# SCH_Pathfinder-V1_2025-12-04.net
KiCad netlist of a schematic drawn in EasyEDA
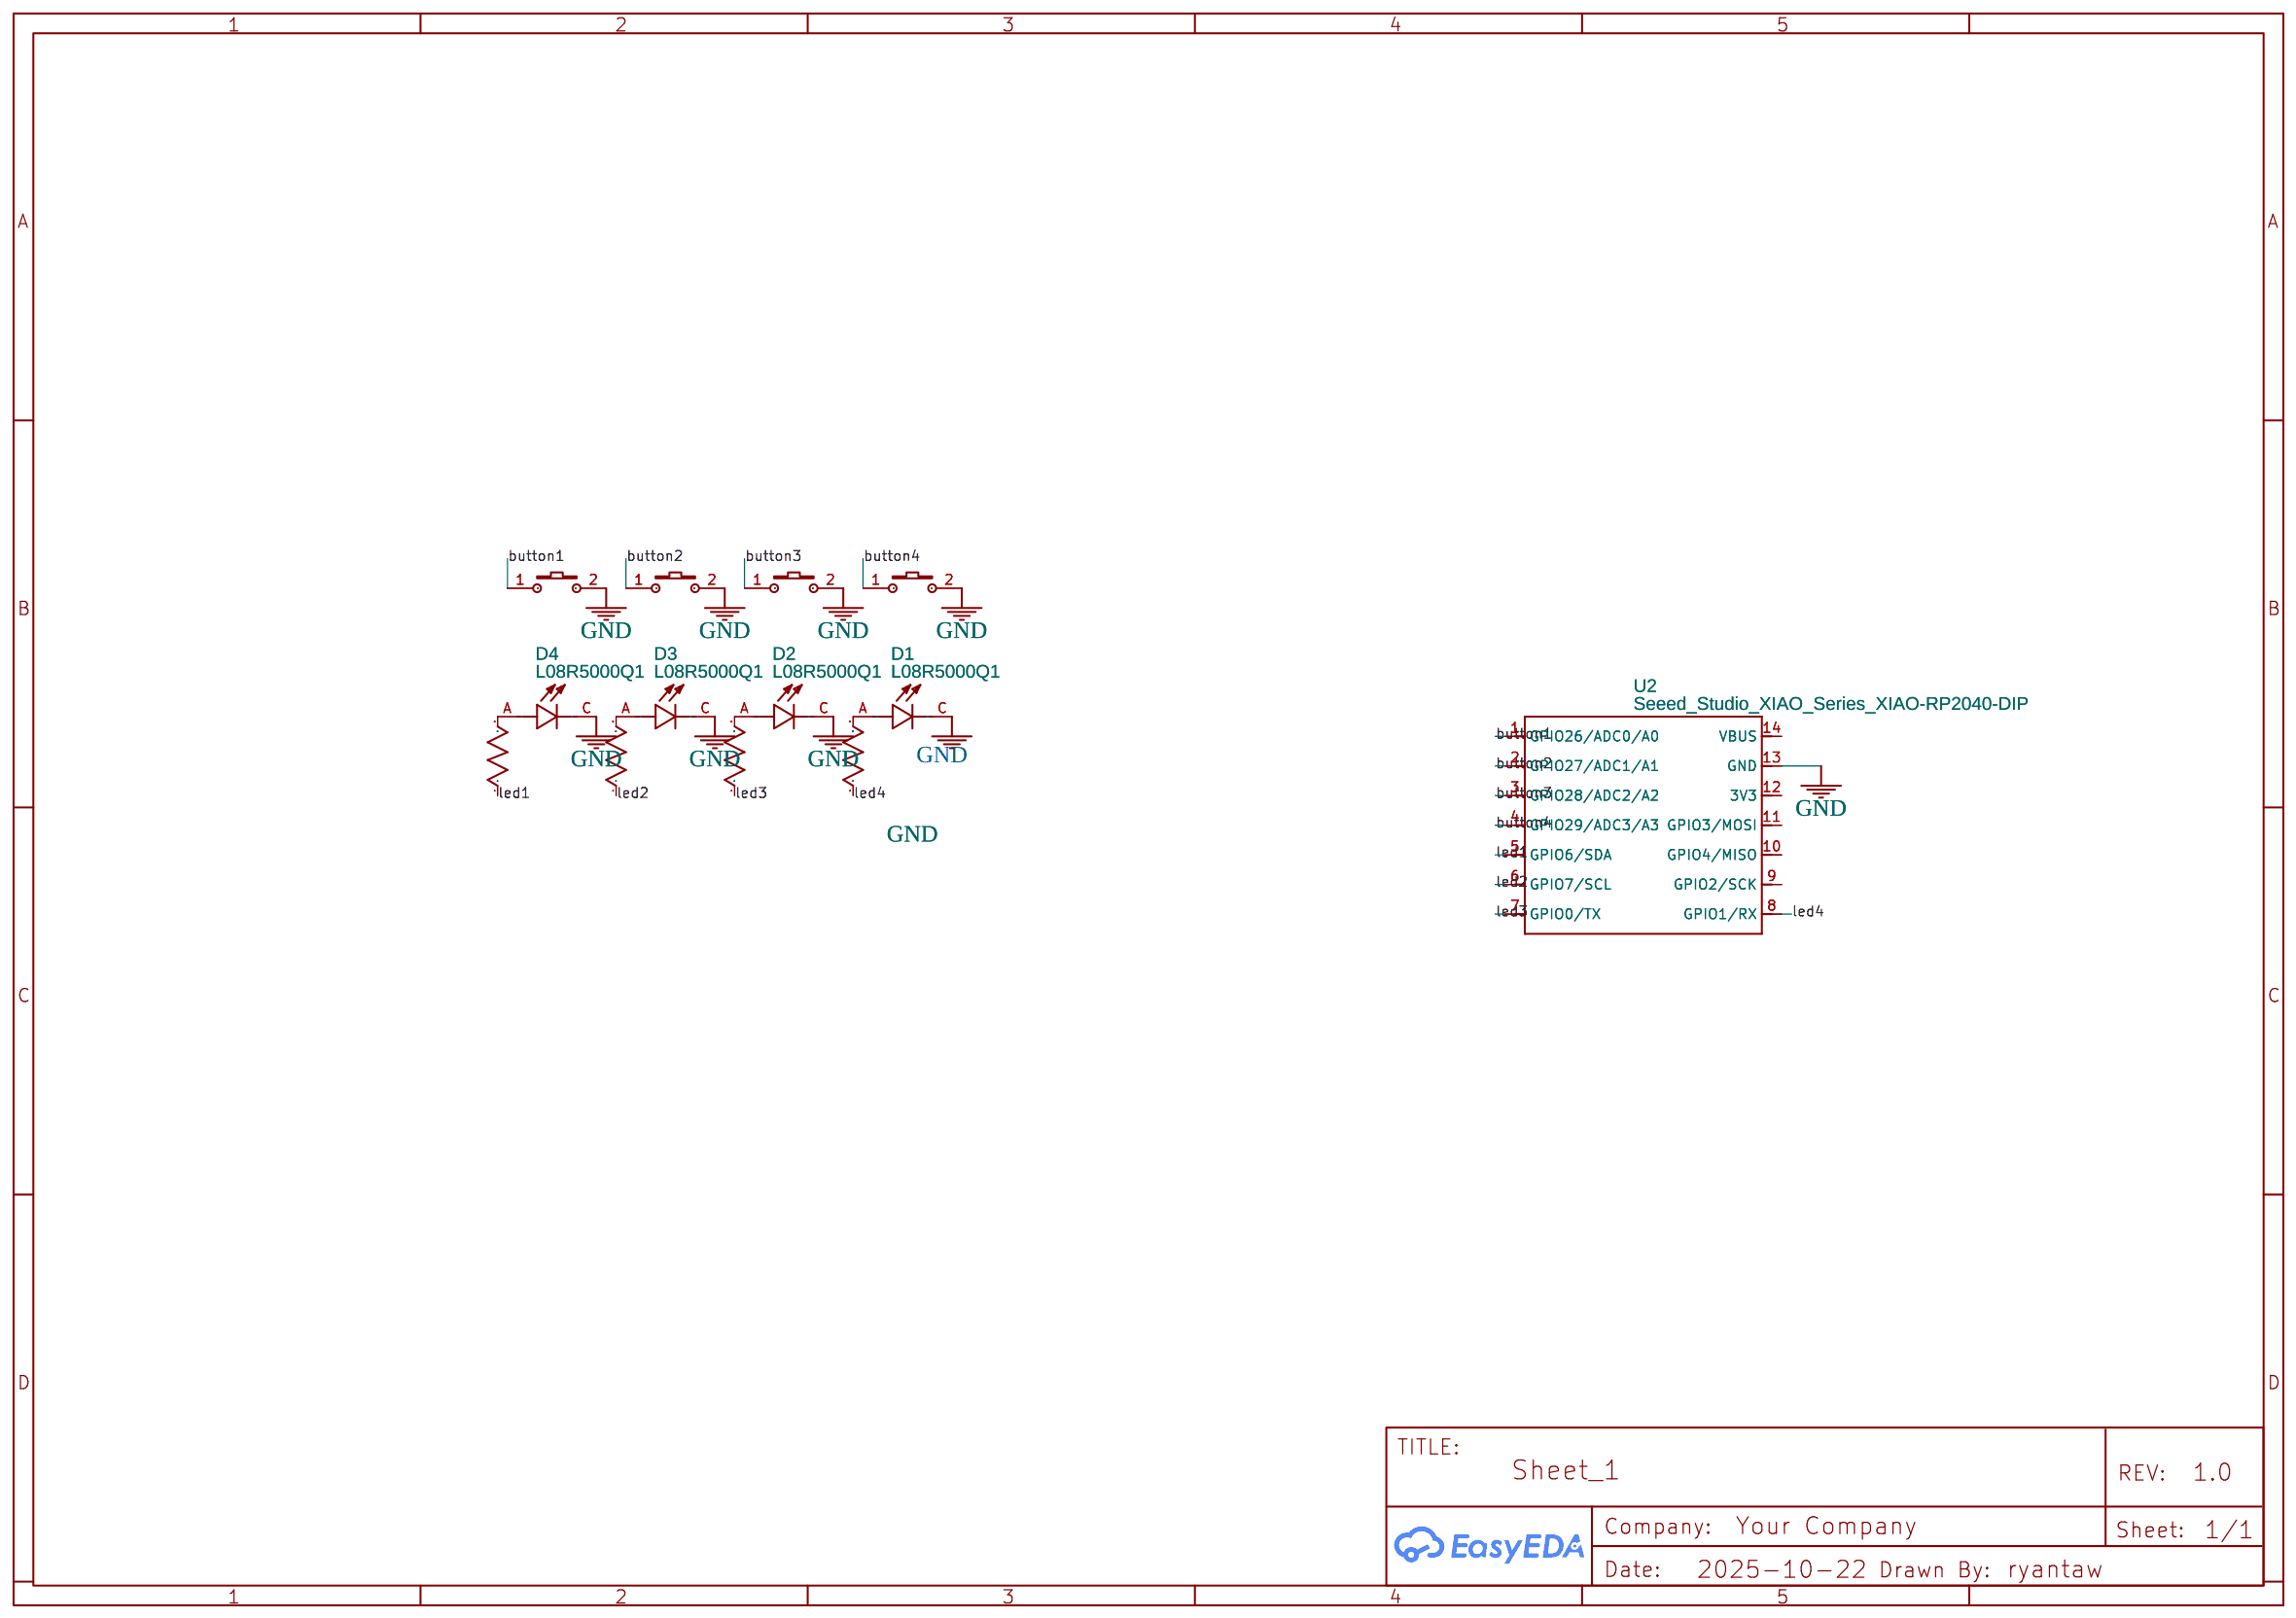
[diagram p0: schematic sheet]

(export (version "E")
  (design (tool "Eeschema 10.0.6"))
  (components
    (comp (ref "D1") (value "L08R5000Q1") (libsource (lib "") (part "L08R5000Q1")))
    (comp (ref "D2") (value "L08R5000Q1") (libsource (lib "") (part "L08R5000Q1")))
    (comp (ref "D3") (value "L08R5000Q1") (libsource (lib "") (part "L08R5000Q1")))
    (comp (ref "D4") (value "L08R5000Q1") (libsource (lib "") (part "L08R5000Q1")))
    (comp (ref "KEY1")
      (value "K2-3.6×6.1_SMD")
      (fields (field (name "Manufacturer Part") "K2-1107ST-A4SW-06"))
      (libsource (lib "") (part "K2-3.6×6.1_SMD"))
    )
    (comp (ref "KEY2")
      (value "K2-3.6×6.1_SMD")
      (fields (field (name "Manufacturer Part") "K2-1107ST-A4SW-06"))
      (libsource (lib "") (part "K2-3.6×6.1_SMD"))
    )
    (comp (ref "KEY3")
      (value "K2-3.6×6.1_SMD")
      (fields (field (name "Manufacturer Part") "K2-1107ST-A4SW-06"))
      (libsource (lib "") (part "K2-3.6×6.1_SMD"))
    )
    (comp (ref "KEY4")
      (value "K2-3.6×6.1_SMD")
      (fields (field (name "Manufacturer Part") "K2-1107ST-A4SW-06"))
      (libsource (lib "") (part "K2-3.6×6.1_SMD"))
    )
    (comp (ref "R1") (value "1k") (libsource (lib "") (part "R_0603_US")))
    (comp (ref "R2") (value "1k") (libsource (lib "") (part "R_0603_US")))
    (comp (ref "R3") (value "1k") (libsource (lib "") (part "R_0603_US")))
    (comp (ref "R4") (value "1k") (libsource (lib "") (part "R_0603_US")))
    (comp (ref "U2")
      (value "Seeed_Studio_XIAO_Series_XIAO-RP2040-DIP")
      (libsource (lib "") (part "Seeed_Studio_XIAO_Series_XIAO-RP2040-DIP"))
    )
  )
  (nets
    (net (code "1") (name "/button1") (class "Default")
      (node (ref "KEY1") (pin "1") (pinfunction "1_1") (pintype "unspecified"))
      (node (ref "U2") (pin "1") (pinfunction "GPIO26/ADC0/A0_1") (pintype "unspecified"))
    )
    (net (code "2") (name "/button2") (class "Default")
      (node (ref "KEY2") (pin "1") (pinfunction "1_1") (pintype "unspecified"))
      (node (ref "U2") (pin "2") (pinfunction "GPIO27/ADC1/A1_2") (pintype "unspecified"))
    )
    (net (code "3") (name "/button3") (class "Default")
      (node (ref "KEY3") (pin "1") (pinfunction "1_1") (pintype "unspecified"))
      (node (ref "U2") (pin "3") (pinfunction "GPIO28/ADC2/A2_3") (pintype "unspecified"))
    )
    (net (code "4") (name "/button4") (class "Default")
      (node (ref "KEY4") (pin "1") (pinfunction "1_1") (pintype "unspecified"))
      (node (ref "U2") (pin "4") (pinfunction "GPIO29/ADC3/A3_4") (pintype "unspecified"))
    )
    (net (code "5") (name "/led1") (class "Default")
      (node (ref "R1") (pin "1") (pinfunction "1_1") (pintype "unspecified"))
      (node (ref "U2") (pin "5") (pinfunction "GPIO6/SDA_5") (pintype "unspecified"))
    )
    (net (code "6") (name "/led2") (class "Default")
      (node (ref "R2") (pin "1") (pinfunction "1_1") (pintype "unspecified"))
      (node (ref "U2") (pin "6") (pinfunction "GPIO7/SCL_6") (pintype "unspecified"))
    )
    (net (code "7") (name "/led3") (class "Default")
      (node (ref "R3") (pin "1") (pinfunction "1_1") (pintype "unspecified"))
      (node (ref "U2") (pin "7") (pinfunction "GPIO0/TX_7") (pintype "unspecified"))
    )
    (net (code "8") (name "/led4") (class "Default")
      (node (ref "R4") (pin "1") (pinfunction "1_1") (pintype "unspecified"))
      (node (ref "U2") (pin "8") (pinfunction "GPIO1/RX_8") (pintype "unspecified"))
    )
    (net (code "9") (name "GND") (class "Default")
      (node (ref "D1") (pin "C") (pinfunction "C_C") (pintype "bidirectional"))
      (node (ref "D2") (pin "C") (pinfunction "C_C") (pintype "bidirectional"))
      (node (ref "D3") (pin "C") (pinfunction "C_C") (pintype "bidirectional"))
      (node (ref "D4") (pin "C") (pinfunction "C_C") (pintype "bidirectional"))
      (node (ref "KEY1") (pin "2") (pinfunction "2_2") (pintype "unspecified"))
      (node (ref "KEY2") (pin "2") (pinfunction "2_2") (pintype "unspecified"))
      (node (ref "KEY3") (pin "2") (pinfunction "2_2") (pintype "unspecified"))
      (node (ref "KEY4") (pin "2") (pinfunction "2_2") (pintype "unspecified"))
      (node (ref "U2") (pin "13") (pinfunction "GND_13") (pintype "unspecified"))
    )
    (net (code "10") (name "Net-(D1-PadA)") (class "Default")
      (node (ref "D1") (pin "A") (pinfunction "A_A") (pintype "bidirectional"))
      (node (ref "R4") (pin "2") (pinfunction "2_2") (pintype "unspecified"))
    )
    (net (code "11") (name "Net-(D2-PadA)") (class "Default")
      (node (ref "D2") (pin "A") (pinfunction "A_A") (pintype "bidirectional"))
      (node (ref "R3") (pin "2") (pinfunction "2_2") (pintype "unspecified"))
    )
    (net (code "12") (name "Net-(D3-PadA)") (class "Default")
      (node (ref "D3") (pin "A") (pinfunction "A_A") (pintype "bidirectional"))
      (node (ref "R2") (pin "2") (pinfunction "2_2") (pintype "unspecified"))
    )
    (net (code "13") (name "Net-(D4-PadA)") (class "Default")
      (node (ref "D4") (pin "A") (pinfunction "A_A") (pintype "bidirectional"))
      (node (ref "R1") (pin "2") (pinfunction "2_2") (pintype "unspecified"))
    )
    (net (code "14") (name "unconnected-(U2-3V3-Pad12)") (class "Default")
      (node (ref "U2") (pin "12") (pinfunction "3V3_12") (pintype "unspecified"))
    )
    (net (code "15") (name "unconnected-(U2-GPIO2{slash}SCK-Pad9)") (class "Default")
      (node (ref "U2") (pin "9") (pinfunction "GPIO2/SCK_9") (pintype "unspecified"))
    )
    (net (code "16") (name "unconnected-(U2-GPIO3{slash}MOSI-Pad11)") (class "Default")
      (node (ref "U2") (pin "11") (pinfunction "GPIO3/MOSI_11") (pintype "unspecified"))
    )
    (net (code "17") (name "unconnected-(U2-GPIO4{slash}MISO-Pad10)") (class "Default")
      (node (ref "U2") (pin "10") (pinfunction "GPIO4/MISO_10") (pintype "unspecified"))
    )
    (net (code "18") (name "unconnected-(U2-VBUS-Pad14)") (class "Default")
      (node (ref "U2") (pin "14") (pinfunction "VBUS_14") (pintype "unspecified"))
    )
  )
)
